# switch.net
KiCad netlist of a schematic drawn in Altium Designer
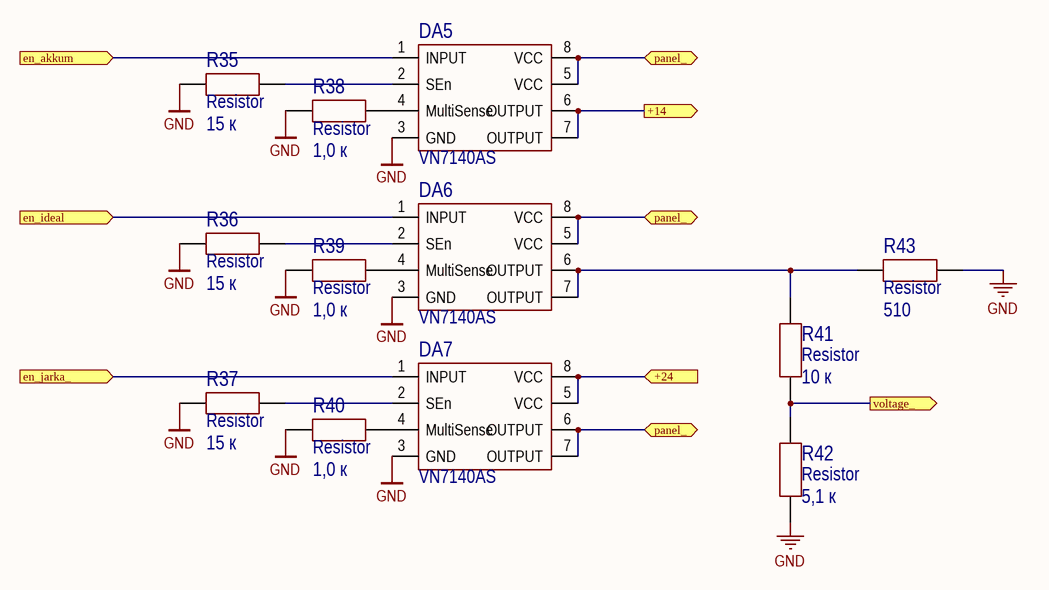
[diagram p0: switch.SchDoc]

(export (version "E")
  (design (tool "Eeschema 10.0.6"))
  (components
    (comp (ref "DA5")
      (value "VN7140AS")
      (footprint "SOP8")
      (description "Силовой ключ верхнего плеча с аналоговой обратной связью MultiSense автомобильного применения")
      (libsource (lib "Hydrolib") (part "VN7140AS"))
    )
    (comp (ref "DA6")
      (value "VN7140AS")
      (footprint "SOP8")
      (description "Силовой ключ верхнего плеча с аналоговой обратной связью MultiSense автомобильного применения")
      (libsource (lib "Hydrolib") (part "VN7140AS"))
    )
    (comp (ref "DA7")
      (value "VN7140AS")
      (footprint "SOP8")
      (description "Силовой ключ верхнего плеча с аналоговой обратной связью MultiSense автомобильного применения")
      (libsource (lib "Hydrolib") (part "VN7140AS"))
    )
    (comp (ref "R35")
      (value "Resistor")
      (footprint "0603R")
      (description "Резистор номиналом 15 кОм и точностью 1%")
      (fields
        (field (name "ALTIUM_VALUE") "15 к")
        (field (name "PART NUMBER") "Resistor_15k_1_0603")
        (field (name "TOLERANCE") "1%")
      )
      (libsource (lib "Hydrolib") (part "Resistor"))
    )
    (comp (ref "R36")
      (value "Resistor")
      (footprint "0603R")
      (description "Резистор номиналом 15 кОм и точностью 1%")
      (fields
        (field (name "ALTIUM_VALUE") "15 к")
        (field (name "PART NUMBER") "Resistor_15k_1_0603")
        (field (name "TOLERANCE") "1%")
      )
      (libsource (lib "Hydrolib") (part "Resistor"))
    )
    (comp (ref "R37")
      (value "Resistor")
      (footprint "0603R")
      (description "Резистор номиналом 15 кОм и точностью 1%")
      (fields
        (field (name "ALTIUM_VALUE") "15 к")
        (field (name "PART NUMBER") "Resistor_15k_1_0603")
        (field (name "TOLERANCE") "1%")
      )
      (libsource (lib "Hydrolib") (part "Resistor"))
    )
    (comp (ref "R38")
      (value "Resistor")
      (footprint "0603R")
      (description "Резистор номиналом 1,0 кОм и точностью 1%")
      (fields
        (field (name "ALTIUM_VALUE") "1,0 к")
        (field (name "PART NUMBER") "Resistor_1.0k_1_0603")
        (field (name "TOLERANCE") "1%")
      )
      (libsource (lib "Hydrolib") (part "Resistor"))
    )
    (comp (ref "R39")
      (value "Resistor")
      (footprint "0603R")
      (description "Резистор номиналом 1,0 кОм и точностью 1%")
      (fields
        (field (name "ALTIUM_VALUE") "1,0 к")
        (field (name "PART NUMBER") "Resistor_1.0k_1_0603")
        (field (name "TOLERANCE") "1%")
      )
      (libsource (lib "Hydrolib") (part "Resistor"))
    )
    (comp (ref "R40")
      (value "Resistor")
      (footprint "0603R")
      (description "Резистор номиналом 1,0 кОм и точностью 1%")
      (fields
        (field (name "ALTIUM_VALUE") "1,0 к")
        (field (name "PART NUMBER") "Resistor_1.0k_1_0603")
        (field (name "TOLERANCE") "1%")
      )
      (libsource (lib "Hydrolib") (part "Resistor"))
    )
    (comp (ref "R41")
      (value "Resistor")
      (footprint "0603R")
      (description "Резистор номиналом 10 кОм и точностью 1%")
      (fields
        (field (name "ALTIUM_VALUE") "10 к")
        (field (name "PART NUMBER") "Resistor_10k_1_0603")
        (field (name "TOLERANCE") "1%")
      )
      (libsource (lib "") (part "Resistor_1"))
    )
    (comp (ref "R42")
      (value "Resistor")
      (footprint "0603R")
      (description "Резистор номиналом 5,1 кОм и точностью 1%")
      (fields
        (field (name "ALTIUM_VALUE") "5,1 к")
        (field (name "PART NUMBER") "Resistor_5.1k_1_0603")
        (field (name "TOLERANCE") "1%")
      )
      (libsource (lib "") (part "Resistor_1"))
    )
    (comp (ref "R43")
      (value "Resistor")
      (footprint "2512R")
      (description "Резистор номиналом 510 Ом и точностью 1%")
      (fields
        (field (name "ALTIUM_VALUE") "510")
        (field (name "PART NUMBER") "Resistor_510_1_0603")
        (field (name "TOLERANCE") "1%")
      )
      (libsource (lib "Hydrolib") (part "Resistor"))
    )
  )
  (nets
    (net (code "1") (name "/+14") (class "Default")
      (node (ref "DA5") (pin "6") (pinfunction "OUTPUT_6") (pintype "passive"))
      (node (ref "DA5") (pin "7") (pinfunction "OUTPUT_7") (pintype "passive"))
    )
    (net (code "2") (name "/+24") (class "Default")
      (node (ref "DA7") (pin "5") (pinfunction "VCC_5") (pintype "passive"))
      (node (ref "DA7") (pin "8") (pinfunction "VCC_8") (pintype "passive"))
    )
    (net (code "3") (name "/en_akkum") (class "Default")
      (node (ref "DA5") (pin "1") (pinfunction "INPUT_1") (pintype "passive"))
    )
    (net (code "4") (name "/en_ideal") (class "Default")
      (node (ref "DA6") (pin "1") (pinfunction "INPUT_1") (pintype "passive"))
    )
    (net (code "5") (name "/en_jarka_") (class "Default")
      (node (ref "DA7") (pin "1") (pinfunction "INPUT_1") (pintype "passive"))
    )
    (net (code "6") (name "/panel_") (class "Default")
      (node (ref "DA5") (pin "5") (pinfunction "VCC_5") (pintype "passive"))
      (node (ref "DA5") (pin "8") (pinfunction "VCC_8") (pintype "passive"))
      (node (ref "DA6") (pin "5") (pinfunction "VCC_5") (pintype "passive"))
      (node (ref "DA6") (pin "8") (pinfunction "VCC_8") (pintype "passive"))
      (node (ref "DA7") (pin "6") (pinfunction "OUTPUT_6") (pintype "passive"))
      (node (ref "DA7") (pin "7") (pinfunction "OUTPUT_7") (pintype "passive"))
    )
    (net (code "7") (name "/voltage_") (class "Default")
      (node (ref "R41") (pin "1") (pinfunction "1_1") (pintype "passive"))
      (node (ref "R42") (pin "2") (pinfunction "2_2") (pintype "passive"))
    )
    (net (code "8") (name "GND") (class "Default")
      (node (ref "DA5") (pin "3") (pinfunction "GND_3") (pintype "passive"))
      (node (ref "DA6") (pin "3") (pinfunction "GND_3") (pintype "passive"))
      (node (ref "DA7") (pin "3") (pinfunction "GND_3") (pintype "passive"))
      (node (ref "R35") (pin "1") (pinfunction "1_1") (pintype "passive"))
      (node (ref "R36") (pin "1") (pinfunction "1_1") (pintype "passive"))
      (node (ref "R37") (pin "1") (pinfunction "1_1") (pintype "passive"))
      (node (ref "R38") (pin "1") (pinfunction "1_1") (pintype "passive"))
      (node (ref "R39") (pin "1") (pinfunction "1_1") (pintype "passive"))
      (node (ref "R40") (pin "1") (pinfunction "1_1") (pintype "passive"))
      (node (ref "R42") (pin "1") (pinfunction "1_1") (pintype "passive"))
      (node (ref "R43") (pin "2") (pinfunction "2_2") (pintype "passive"))
    )
    (net (code "9") (name "Net-(DA5-MultiSense)") (class "Default")
      (node (ref "DA5") (pin "4") (pinfunction "MultiSense_4") (pintype "passive"))
      (node (ref "R38") (pin "2") (pinfunction "2_2") (pintype "passive"))
    )
    (net (code "10") (name "Net-(DA5-SEn)") (class "Default")
      (node (ref "DA5") (pin "2") (pinfunction "SEn_2") (pintype "passive"))
      (node (ref "R35") (pin "2") (pinfunction "2_2") (pintype "passive"))
    )
    (net (code "11") (name "Net-(DA6-MultiSense)") (class "Default")
      (node (ref "DA6") (pin "4") (pinfunction "MultiSense_4") (pintype "passive"))
      (node (ref "R39") (pin "2") (pinfunction "2_2") (pintype "passive"))
    )
    (net (code "12") (name "Net-(DA6-OUTPUT-Pad6)") (class "Default")
      (node (ref "DA6") (pin "6") (pinfunction "OUTPUT_6") (pintype "passive"))
      (node (ref "DA6") (pin "7") (pinfunction "OUTPUT_7") (pintype "passive"))
      (node (ref "R41") (pin "2") (pinfunction "2_2") (pintype "passive"))
      (node (ref "R43") (pin "1") (pinfunction "1_1") (pintype "passive"))
    )
    (net (code "13") (name "Net-(DA6-SEn)") (class "Default")
      (node (ref "DA6") (pin "2") (pinfunction "SEn_2") (pintype "passive"))
      (node (ref "R36") (pin "2") (pinfunction "2_2") (pintype "passive"))
    )
    (net (code "14") (name "Net-(DA7-MultiSense)") (class "Default")
      (node (ref "DA7") (pin "4") (pinfunction "MultiSense_4") (pintype "passive"))
      (node (ref "R40") (pin "2") (pinfunction "2_2") (pintype "passive"))
    )
    (net (code "15") (name "Net-(DA7-SEn)") (class "Default")
      (node (ref "DA7") (pin "2") (pinfunction "SEn_2") (pintype "passive"))
      (node (ref "R37") (pin "2") (pinfunction "2_2") (pintype "passive"))
    )
  )
)
